# M_h_Tas_-_1.net
KiCad netlist of a schematic drawn in Altium Designer
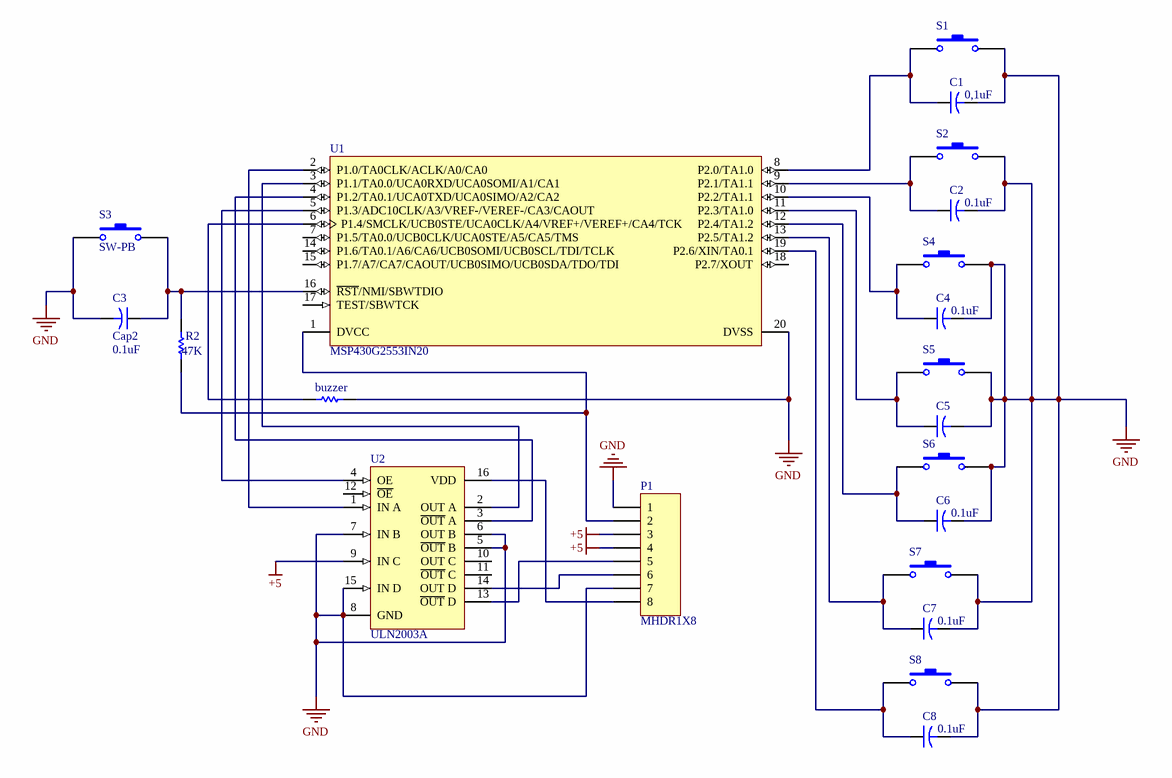
[diagram p0: Müh Tas - 1.SchDoc]

(export (version "E")
  (design (tool "Eeschema 10.0.6"))
  (components
    (comp (ref "buzzer")
      (value "Res1")
      (footprint "AXIAL-0.3")
      (description "Resistor")
      (fields (field (name "PUBLISHER") "Altium Limited"))
      (libsource (lib "Miscellaneous Devices") (part "Res1"))
    )
    (comp (ref "C1")
      (value "0,1uF")
      (footprint "CAPR5-4X5")
      (description "Capacitor")
      (fields (field (name "Comment") "Cap2") (field (name "PUBLISHER") "Altium Limited"))
      (libsource (lib "Miscellaneous Devices") (part "Cap2"))
    )
    (comp (ref "C2")
      (value "0.1uF")
      (footprint "CAPR5-4X5")
      (description "Capacitor")
      (fields (field (name "Comment") "Cap2") (field (name "PUBLISHER") "Altium Limited"))
      (libsource (lib "Miscellaneous Devices") (part "Cap2"))
    )
    (comp (ref "C3")
      (value "Cap2")
      (footprint "CAPR5-4X5")
      (description "Capacitor")
      (fields (field (name "ALTIUM_VALUE") "0.1uF") (field (name "PUBLISHER") "Altium Limited"))
      (libsource (lib "Miscellaneous Devices") (part "Cap2"))
    )
    (comp (ref "C4")
      (value "0.1uF")
      (footprint "CAPR5-4X5")
      (description "Capacitor")
      (fields (field (name "Comment") "Cap2") (field (name "PUBLISHER") "Altium Limited"))
      (libsource (lib "Miscellaneous Devices") (part "Cap2"))
    )
    (comp (ref "C5")
      (value "Cap2")
      (footprint "CAPR5-4X5")
      (description "Capacitor")
      (fields (field (name "PUBLISHER") "Altium Limited"))
      (libsource (lib "Miscellaneous Devices") (part "Cap2"))
    )
    (comp (ref "C6")
      (value "0.1uF")
      (footprint "CAPR5-4X5")
      (description "Capacitor")
      (fields (field (name "Comment") "Cap2") (field (name "PUBLISHER") "Altium Limited"))
      (libsource (lib "Miscellaneous Devices") (part "Cap2"))
    )
    (comp (ref "C7")
      (value "0.1uF")
      (footprint "CAPR5-4X5")
      (description "Capacitor")
      (fields (field (name "Comment") "Cap2") (field (name "PUBLISHER") "Altium Limited"))
      (libsource (lib "Miscellaneous Devices") (part "Cap2"))
    )
    (comp (ref "C8")
      (value "0.1uF")
      (footprint "CAPR5-4X5")
      (description "Capacitor")
      (fields (field (name "Comment") "Cap2") (field (name "PUBLISHER") "Altium Limited"))
      (libsource (lib "Miscellaneous Devices") (part "Cap2"))
    )
    (comp (ref "P1")
      (value "MHDR1X8")
      (footprint "MHDR1X8")
      (description "Header, 8-Pin")
      (fields (field (name "PUBLISHER") "Altium Limited"))
      (libsource (lib "Miscellaneous Connectors") (part "MHDR1X8"))
    )
    (comp (ref "R2")
      (value "47K")
      (footprint "AXIAL-0.3")
      (description "Resistor")
      (fields (field (name "Comment") "Res1") (field (name "PUBLISHER") "Altium Limited"))
      (libsource (lib "Miscellaneous Devices") (part "Res1"))
    )
    (comp (ref "S1")
      (value "SW-PB")
      (footprint "SPST-2")
      (description "Switch")
      (fields (field (name "PUBLISHER") "Altium Limited"))
      (libsource (lib "Miscellaneous Devices") (part "SW-PB"))
    )
    (comp (ref "S2")
      (value "SW-PB")
      (footprint "SPST-2")
      (description "Switch")
      (fields (field (name "PUBLISHER") "Altium Limited"))
      (libsource (lib "Miscellaneous Devices") (part "SW-PB"))
    )
    (comp (ref "S3")
      (value "SW-PB")
      (footprint "SPST-2")
      (description "Switch")
      (fields (field (name "PUBLISHER") "Altium Limited"))
      (libsource (lib "Miscellaneous Devices") (part "SW-PB"))
    )
    (comp (ref "S4")
      (value "SW-PB")
      (footprint "SPST-2")
      (description "Switch")
      (fields (field (name "PUBLISHER") "Altium Limited"))
      (libsource (lib "Miscellaneous Devices") (part "SW-PB"))
    )
    (comp (ref "S5")
      (value "SW-PB")
      (footprint "SPST-2")
      (description "Switch")
      (fields (field (name "PUBLISHER") "Altium Limited"))
      (libsource (lib "Miscellaneous Devices") (part "SW-PB"))
    )
    (comp (ref "S6")
      (value "SW-PB")
      (footprint "SPST-2")
      (description "Switch")
      (fields (field (name "PUBLISHER") "Altium Limited"))
      (libsource (lib "Miscellaneous Devices") (part "SW-PB"))
    )
    (comp (ref "S7")
      (value "SW-PB")
      (footprint "SPST-2")
      (description "Switch")
      (fields (field (name "PUBLISHER") "Altium Limited"))
      (libsource (lib "Miscellaneous Devices") (part "SW-PB"))
    )
    (comp (ref "S8")
      (value "SW-PB")
      (footprint "SPST-2")
      (description "Switch")
      (fields (field (name "PUBLISHER") "Altium Limited"))
      (libsource (lib "Miscellaneous Devices") (part "SW-PB"))
    )
    (comp (ref "U1")
      (value "MSP430G2553IN20")
      (footprint "TI-N20")
      (fields (field (name "MANUFACTURER") "Texas Instruments"))
      (libsource (lib "TI Microcontroller MSP430 16-bit Ultra-Low Power") (part "MSP430G2553IN20"))
    )
    (comp (ref "U2")
      (value "ULN2003A")
      (footprint "620-10")
      (description "Quad EIA-422 Line Driver with Three-State Output")
      (fields (field (name "PUBLISHER") "Altium Limited"))
      (libsource (lib "Motorola Logic Buffer Line Driver") (part "AM26LS31DC"))
    )
  )
  (nets
    (net (code "1") (name "+5") (class "Default")
      (node (ref "P1") (pin "3") (pinfunction "3_3") (pintype "passive"))
      (node (ref "P1") (pin "4") (pinfunction "4_4") (pintype "passive"))
      (node (ref "U2") (pin "9") (pinfunction "IN_C_9") (pintype "input"))
    )
    (net (code "2") (name "GND") (class "Default")
      (node (ref "C1") (pin "2") (pinfunction "2_2") (pintype "passive"))
      (node (ref "C2") (pin "2") (pinfunction "2_2") (pintype "passive"))
      (node (ref "C3") (pin "2") (pinfunction "2_2") (pintype "passive"))
      (node (ref "C4") (pin "2") (pinfunction "2_2") (pintype "passive"))
      (node (ref "C5") (pin "2") (pinfunction "2_2") (pintype "passive"))
      (node (ref "C6") (pin "2") (pinfunction "2_2") (pintype "passive"))
      (node (ref "C7") (pin "2") (pinfunction "2_2") (pintype "passive"))
      (node (ref "C8") (pin "2") (pinfunction "2_2") (pintype "passive"))
      (node (ref "P1") (pin "1") (pinfunction "1_1") (pintype "passive"))
      (node (ref "P1") (pin "7") (pinfunction "7_7") (pintype "passive"))
      (node (ref "S1") (pin "2") (pinfunction "2_2") (pintype "passive"))
      (node (ref "S2") (pin "2") (pinfunction "2_2") (pintype "passive"))
      (node (ref "S3") (pin "1") (pinfunction "1_1") (pintype "passive"))
      (node (ref "S4") (pin "2") (pinfunction "2_2") (pintype "passive"))
      (node (ref "S5") (pin "2") (pinfunction "2_2") (pintype "passive"))
      (node (ref "S6") (pin "2") (pinfunction "2_2") (pintype "passive"))
      (node (ref "S7") (pin "2") (pinfunction "2_2") (pintype "passive"))
      (node (ref "S8") (pin "2") (pinfunction "2_2") (pintype "passive"))
      (node (ref "U1") (pin "20") (pinfunction "DVSS_20") (pintype "power_in"))
      (node (ref "U2") (pin "15") (pinfunction "IN_D_15") (pintype "input"))
      (node (ref "U2") (pin "5") (pinfunction "~{OUT}_B_5") (pintype "tri_state"))
      (node (ref "U2") (pin "6") (pinfunction "OUT_B_6") (pintype "tri_state"))
      (node (ref "U2") (pin "7") (pinfunction "IN_B_7") (pintype "input"))
      (node (ref "U2") (pin "8") (pinfunction "GND_8") (pintype "power_in"))
      (node (ref "buzzer") (pin "2") (pinfunction "2_2") (pintype "passive"))
    )
    (net (code "3") (name "Net-(U1-DVCC)") (class "Default")
      (node (ref "P1") (pin "2") (pinfunction "2_2") (pintype "passive"))
      (node (ref "R2") (pin "2") (pinfunction "2_2") (pintype "passive"))
      (node (ref "U1") (pin "1") (pinfunction "DVCC_1") (pintype "power_in"))
    )
    (net (code "4") (name "Net-(U1-P1.0{slash}TA0CLK{slash}ACLK{slash}A0{slash}CA0)") (class "Default")
      (node (ref "U1") (pin "2") (pinfunction "P1.0/TA0CLK/ACLK/A0/CA0_2") (pintype "bidirectional"))
      (node (ref "U2") (pin "1") (pinfunction "IN_A_1") (pintype "input"))
    )
    (net (code "5") (name "Net-(U1-P1.1{slash}TA0.0{slash}UCA0RXD{slash}UCA0SOMI{slash}A1{slash}CA1)") (class "Default")
      (node (ref "U1") (pin "3") (pinfunction "P1.1/TA0.0/UCA0RXD/UCA0SOMI/A1/CA1_3") (pintype "bidirectional"))
      (node (ref "U2") (pin "2") (pinfunction "OUT_A_2") (pintype "tri_state"))
    )
    (net (code "6") (name "Net-(U1-P1.2{slash}TA0.1{slash}UCA0TXD{slash}UCA0SIMO{slash}A2{slash}CA2)") (class "Default")
      (node (ref "U1") (pin "4") (pinfunction "P1.2/TA0.1/UCA0TXD/UCA0SIMO/A2/CA2_4") (pintype "bidirectional"))
      (node (ref "U2") (pin "3") (pinfunction "~{OUT}_A_3") (pintype "tri_state"))
    )
    (net (code "7") (name "Net-(U1-P1.3{slash}ADC10CLK{slash}A3{slash}VREF-{slash}VEREF-{slash}CA3{slash}CAOUT)") (class "Default")
      (node (ref "U1") (pin "5") (pinfunction "P1.3/ADC10CLK/A3/VREF-/VEREF-/CA3/CAOUT_5") (pintype "bidirectional"))
      (node (ref "U2") (pin "4") (pinfunction "OE_4") (pintype "input"))
    )
    (net (code "8") (name "Net-(U1-P1.4{slash}SMCLK{slash}UCB0STE{slash}UCA0CLK{slash}A4{slash}VREF+{slash}VEREF+{slash}CA4{slash}TCK)") (class "Default")
      (node (ref "U1") (pin "6") (pinfunction "P1.4/SMCLK/UCB0STE/UCA0CLK/A4/VREF+/VEREF+/CA4/TCK_6") (pintype "bidirectional"))
      (node (ref "buzzer") (pin "1") (pinfunction "1_1") (pintype "passive"))
    )
    (net (code "9") (name "Net-(U1-P2.0{slash}TA1.0)") (class "Default")
      (node (ref "C1") (pin "1") (pinfunction "1_1") (pintype "passive"))
      (node (ref "S1") (pin "1") (pinfunction "1_1") (pintype "passive"))
      (node (ref "U1") (pin "8") (pinfunction "P2.0/TA1.0_8") (pintype "bidirectional"))
    )
    (net (code "10") (name "Net-(U1-P2.1{slash}TA1.1)") (class "Default")
      (node (ref "C2") (pin "1") (pinfunction "1_1") (pintype "passive"))
      (node (ref "S2") (pin "1") (pinfunction "1_1") (pintype "passive"))
      (node (ref "U1") (pin "9") (pinfunction "P2.1/TA1.1_9") (pintype "bidirectional"))
    )
    (net (code "11") (name "Net-(U1-P2.2{slash}TA1.1)") (class "Default")
      (node (ref "C4") (pin "1") (pinfunction "1_1") (pintype "passive"))
      (node (ref "S4") (pin "1") (pinfunction "1_1") (pintype "passive"))
      (node (ref "U1") (pin "10") (pinfunction "P2.2/TA1.1_10") (pintype "bidirectional"))
    )
    (net (code "12") (name "Net-(U1-P2.3{slash}TA1.0)") (class "Default")
      (node (ref "C5") (pin "1") (pinfunction "1_1") (pintype "passive"))
      (node (ref "S5") (pin "1") (pinfunction "1_1") (pintype "passive"))
      (node (ref "U1") (pin "11") (pinfunction "P2.3/TA1.0_11") (pintype "bidirectional"))
    )
    (net (code "13") (name "Net-(U1-P2.4{slash}TA1.2)") (class "Default")
      (node (ref "C6") (pin "1") (pinfunction "1_1") (pintype "passive"))
      (node (ref "S6") (pin "1") (pinfunction "1_1") (pintype "passive"))
      (node (ref "U1") (pin "12") (pinfunction "P2.4/TA1.2_12") (pintype "bidirectional"))
    )
    (net (code "14") (name "Net-(U1-P2.5{slash}TA1.2)") (class "Default")
      (node (ref "C7") (pin "1") (pinfunction "1_1") (pintype "passive"))
      (node (ref "S7") (pin "1") (pinfunction "1_1") (pintype "passive"))
      (node (ref "U1") (pin "13") (pinfunction "P2.5/TA1.2_13") (pintype "bidirectional"))
    )
    (net (code "15") (name "Net-(U1-P2.6{slash}XIN{slash}TA0.1)") (class "Default")
      (node (ref "C8") (pin "1") (pinfunction "1_1") (pintype "passive"))
      (node (ref "S8") (pin "1") (pinfunction "1_1") (pintype "passive"))
      (node (ref "U1") (pin "19") (pinfunction "P2.6/XIN/TA0.1_19") (pintype "bidirectional"))
    )
    (net (code "16") (name "Net-(U1-~{RST}{slash}NMI{slash}SBWTDIO)") (class "Default")
      (node (ref "C3") (pin "1") (pinfunction "1_1") (pintype "passive"))
      (node (ref "R2") (pin "1") (pinfunction "1_1") (pintype "passive"))
      (node (ref "S3") (pin "2") (pinfunction "2_2") (pintype "passive"))
      (node (ref "U1") (pin "16") (pinfunction "~{RST}/NMI/SBWTDIO_16") (pintype "bidirectional"))
    )
    (net (code "17") (name "Net-(U2-OUT_D)") (class "Default")
      (node (ref "P1") (pin "6") (pinfunction "6_6") (pintype "passive"))
      (node (ref "U2") (pin "14") (pinfunction "OUT_D_14") (pintype "tri_state"))
    )
    (net (code "18") (name "Net-(U2-VDD)") (class "Default")
      (node (ref "P1") (pin "8") (pinfunction "8_8") (pintype "passive"))
      (node (ref "U2") (pin "16") (pinfunction "VDD_16") (pintype "power_in"))
    )
    (net (code "19") (name "Net-(U2-~{OUT}_D)") (class "Default")
      (node (ref "P1") (pin "5") (pinfunction "5_5") (pintype "passive"))
      (node (ref "U2") (pin "13") (pinfunction "~{OUT}_D_13") (pintype "tri_state"))
    )
    (net (code "20") (name "unconnected-(U1-P1.5{slash}TA0.0{slash}UCB0CLK{slash}UCA0STE{slash}A5{slash}CA5{slash}TMS-Pad7)") (class "Default")
      (node (ref "U1") (pin "7") (pinfunction "P1.5/TA0.0/UCB0CLK/UCA0STE/A5/CA5/TMS_7") (pintype "bidirectional"))
    )
    (net (code "21") (name "unconnected-(U1-P1.6{slash}TA0.1{slash}A6{slash}CA6{slash}UCB0SOMI{slash}UCB0SCL{slash}TDI{slash}TCLK-Pad14)") (class "Default")
      (node (ref "U1") (pin "14") (pinfunction "P1.6/TA0.1/A6/CA6/UCB0SOMI/UCB0SCL/TDI/TCLK_14") (pintype "bidirectional"))
    )
    (net (code "22") (name "unconnected-(U1-P1.7{slash}A7{slash}CA7{slash}CAOUT{slash}UCB0SIMO{slash}UCB0SDA{slash}TDO{slash}TDI-Pad15)") (class "Default")
      (node (ref "U1") (pin "15") (pinfunction "P1.7/A7/CA7/CAOUT/UCB0SIMO/UCB0SDA/TDO/TDI_15") (pintype "bidirectional"))
    )
    (net (code "23") (name "unconnected-(U1-P2.7{slash}XOUT-Pad18)") (class "Default")
      (node (ref "U1") (pin "18") (pinfunction "P2.7/XOUT_18") (pintype "bidirectional"))
    )
    (net (code "24") (name "unconnected-(U1-TEST{slash}SBWTCK-Pad17)") (class "Default")
      (node (ref "U1") (pin "17") (pinfunction "TEST/SBWTCK_17") (pintype "input"))
    )
    (net (code "25") (name "unconnected-(U2-OUT_C-Pad10)") (class "Default")
      (node (ref "U2") (pin "10") (pinfunction "OUT_C_10") (pintype "tri_state"))
    )
    (net (code "26") (name "unconnected-(U2-~{OE}-Pad12)") (class "Default")
      (node (ref "U2") (pin "12") (pinfunction "~{OE}_12") (pintype "input"))
    )
    (net (code "27") (name "unconnected-(U2-~{OUT}_C-Pad11)") (class "Default")
      (node (ref "U2") (pin "11") (pinfunction "~{OUT}_C_11") (pintype "tri_state"))
    )
  )
)
